# Wisp_v03.net
KiCad netlist of a schematic drawn in EAGLE
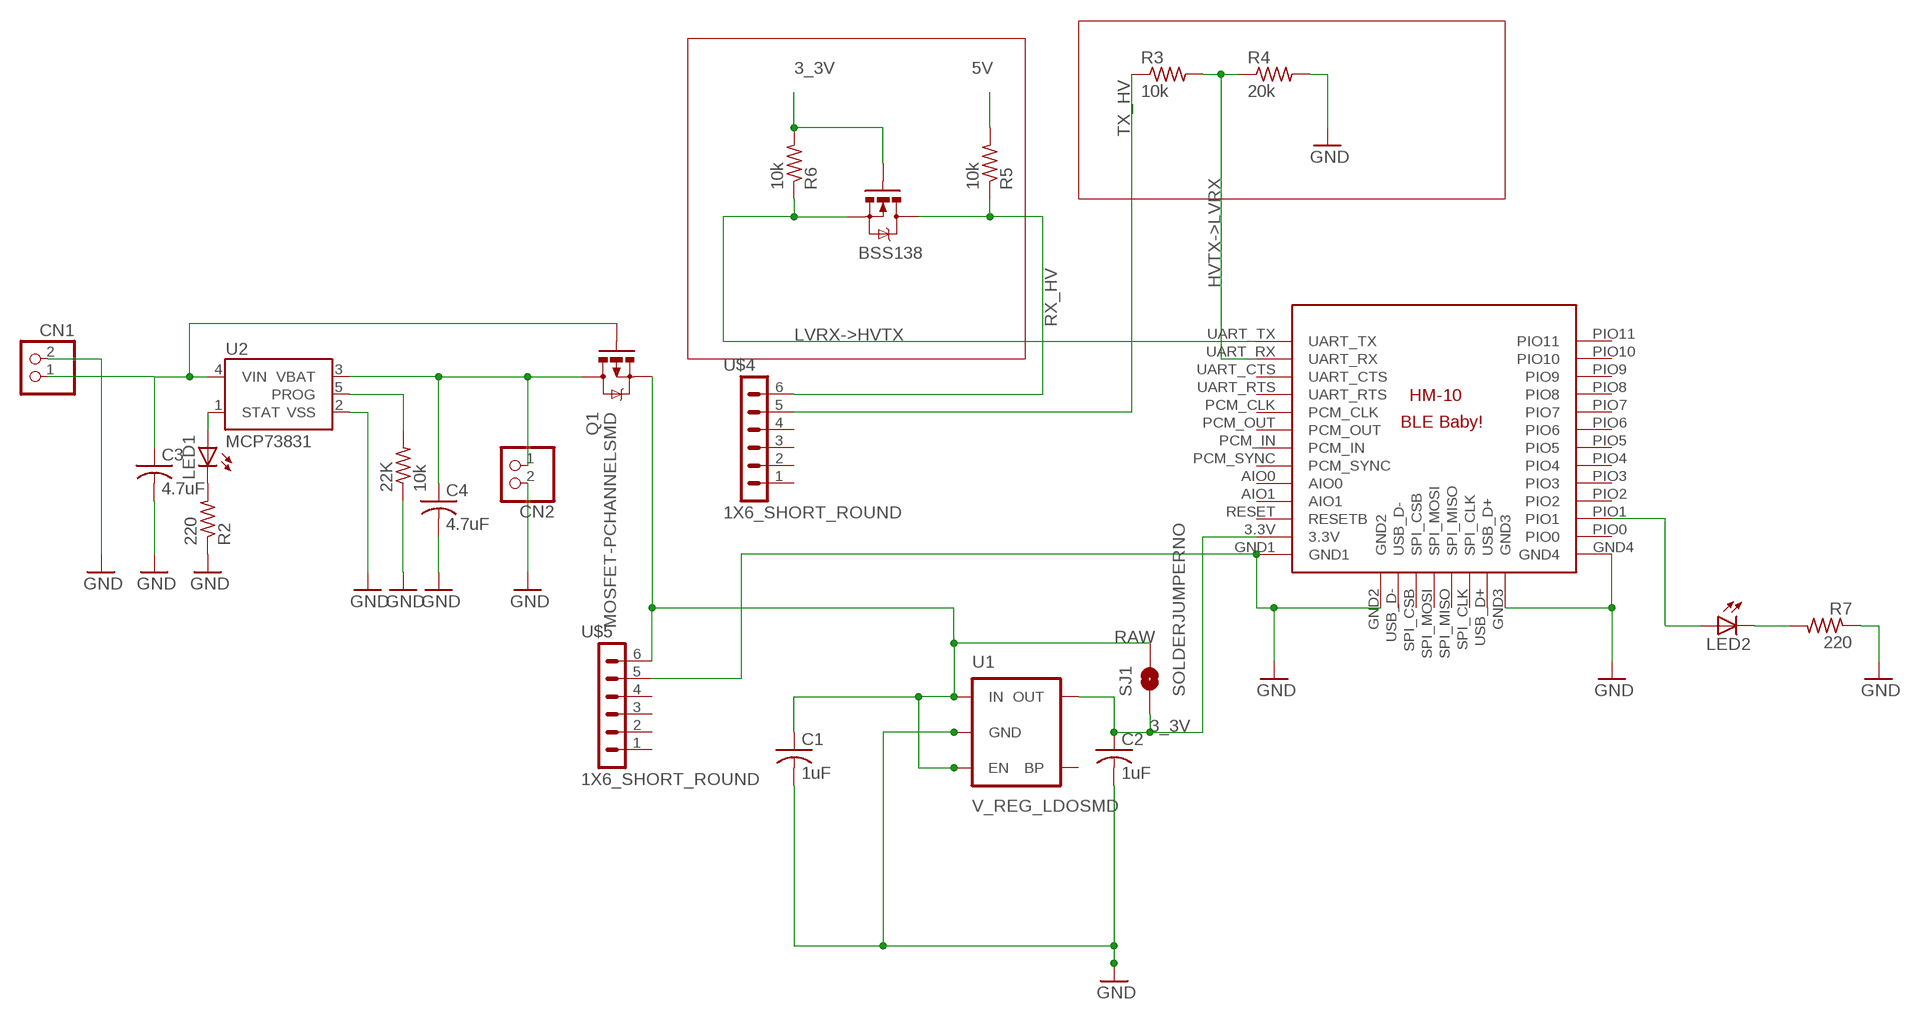
[diagram p0: schematic, sheet 1]

(export (version "E")
  (design (tool "Eeschema 10.0.6"))
  (components
    (comp (ref "22K")
      (value "10k")
      (footprint "eagle-import:R0402")
      (libsource (lib "eagle-import") (part "R-US_R0402"))
    )
    (comp (ref "BSS138")
      (value "MOSFET-NCHANNELSMD")
      (footprint "eagle-import:SOT23-3")
      (libsource (lib "eagle-import") (part "MOSFET-NCHANNELSMD"))
    )
    (comp (ref "C1")
      (value "1uF")
      (footprint "eagle-import:C0805K")
      (libsource (lib "eagle-import") (part "C-USC0805K"))
    )
    (comp (ref "C2")
      (value "1uF")
      (footprint "eagle-import:C0805K")
      (libsource (lib "eagle-import") (part "C-USC0805K"))
    )
    (comp (ref "C3")
      (value "4.7uF")
      (footprint "eagle-import:C0805K")
      (libsource (lib "eagle-import") (part "C-USC0805K"))
    )
    (comp (ref "C4")
      (value "4.7uF")
      (footprint "eagle-import:C0805K")
      (libsource (lib "eagle-import") (part "C-USC0805K"))
    )
    (comp (ref "CN1")
      (value "JST_2PIN-THM")
      (footprint "eagle-import:JST-PH-2-THM")
      (libsource (lib "eagle-import") (part "JST_2PIN-THM"))
    )
    (comp (ref "CN2")
      (value "JST_2PIN-THM")
      (footprint "eagle-import:JST-PH-2-THM")
      (libsource (lib "eagle-import") (part "JST_2PIN-THM"))
    )
    (comp (ref "LED1")
      (value "LED0603")
      (footprint "eagle-import:LED-0603")
      (libsource (lib "eagle-import") (part "LED0603"))
    )
    (comp (ref "LED2")
      (value "LED0603")
      (footprint "eagle-import:LED-0603")
      (libsource (lib "eagle-import") (part "LED0603"))
    )
    (comp (ref "Q1")
      (value "MOSFET-PCHANNELSMD")
      (footprint "eagle-import:SOT23-3")
      (libsource (lib "eagle-import") (part "MOSFET-PCHANNELSMD"))
    )
    (comp (ref "R2")
      (value "220")
      (footprint "eagle-import:R0402")
      (libsource (lib "eagle-import") (part "R-US_R0402"))
    )
    (comp (ref "R3")
      (value "10k")
      (footprint "eagle-import:R0402")
      (libsource (lib "eagle-import") (part "R-US_R0402"))
    )
    (comp (ref "R4")
      (value "20k")
      (footprint "eagle-import:R0402")
      (libsource (lib "eagle-import") (part "R-US_R0402"))
    )
    (comp (ref "R5")
      (value "10k")
      (footprint "eagle-import:R0402")
      (libsource (lib "eagle-import") (part "R-US_R0402"))
    )
    (comp (ref "R6")
      (value "10k")
      (footprint "eagle-import:R0402")
      (libsource (lib "eagle-import") (part "R-US_R0402"))
    )
    (comp (ref "R7")
      (value "220")
      (footprint "eagle-import:R0402")
      (libsource (lib "eagle-import") (part "R-US_R0402"))
    )
    (comp (ref "SJ1")
      (value "SOLDERJUMPERNO")
      (footprint "eagle-import:SJ_2S-NO")
      (libsource (lib "eagle-import") (part "SOLDERJUMPERNO"))
    )
    (comp (ref "U$1")
      (value "BLE-HM-10")
      (footprint "eagle-import:BLE-HM-10")
      (libsource (lib "eagle-import") (part "BLE-HM-10"))
    )
    (comp (ref "U$4")
      (value "1X6_SHORT_ROUND")
      (footprint "eagle-import:1X6_SHORT_ROUND")
      (libsource (lib "eagle-import") (part "1X6_SHORT_ROUND"))
    )
    (comp (ref "U$5")
      (value "1X6_SHORT_ROUND")
      (footprint "eagle-import:1X6_SHORT_ROUND")
      (libsource (lib "eagle-import") (part "1X6_SHORT_ROUND"))
    )
    (comp (ref "U1")
      (value "V_REG_LDOSMD")
      (footprint "eagle-import:SOT23-5")
      (libsource (lib "eagle-import") (part "V_REG_LDOSMD"))
    )
    (comp (ref "U2")
      (value "MCP73831")
      (footprint "eagle-import:SOT23-5")
      (libsource (lib "eagle-import") (part "MCP73831"))
    )
  )
  (nets
    (net (code "1") (name "/3_3V") (class "Default")
      (node (ref "BSS138") (pin "1") (pinfunction "G_1") (pintype "passive"))
      (node (ref "C2") (pin "1") (pinfunction "1_1") (pintype "passive"))
      (node (ref "R6") (pin "2") (pinfunction "2_2") (pintype "passive"))
      (node (ref "SJ1") (pin "1") (pinfunction "1_1") (pintype "passive"))
      (node (ref "U$1") (pin "3.3V") (pinfunction "3.3V_3.3V") (pintype "bidirectional"))
      (node (ref "U1") (pin "5") (pinfunction "OUT_5") (pintype "passive"))
    )
    (net (code "2") (name "/5V") (class "Default")
      (node (ref "R5") (pin "2") (pinfunction "2_2") (pintype "passive"))
    )
    (net (code "3") (name "/HVTX->LVRX") (class "Default")
      (node (ref "R3") (pin "2") (pinfunction "2_2") (pintype "passive"))
      (node (ref "R4") (pin "1") (pinfunction "1_1") (pintype "passive"))
      (node (ref "U$1") (pin "UART_RX") (pinfunction "UART_RX_UART_RX") (pintype "bidirectional"))
    )
    (net (code "4") (name "/LVRX->HVTX") (class "Default")
      (node (ref "BSS138") (pin "2") (pinfunction "S_2") (pintype "passive"))
      (node (ref "R6") (pin "1") (pinfunction "1_1") (pintype "passive"))
      (node (ref "U$1") (pin "UART_TX") (pinfunction "UART_TX_UART_TX") (pintype "bidirectional"))
    )
    (net (code "5") (name "/RAW") (class "Default")
      (node (ref "C1") (pin "1") (pinfunction "1_1") (pintype "passive"))
      (node (ref "Q1") (pin "2") (pinfunction "S_2") (pintype "passive"))
      (node (ref "SJ1") (pin "2") (pinfunction "2_2") (pintype "passive"))
      (node (ref "U$5") (pin "6") (pinfunction "6_6") (pintype "passive"))
      (node (ref "U1") (pin "1") (pinfunction "IN_1") (pintype "input"))
      (node (ref "U1") (pin "3") (pinfunction "EN_3") (pintype "input"))
    )
    (net (code "6") (name "/RX_HV") (class "Default")
      (node (ref "BSS138") (pin "3") (pinfunction "D_3") (pintype "passive"))
      (node (ref "R5") (pin "1") (pinfunction "1_1") (pintype "passive"))
      (node (ref "U$4") (pin "6") (pinfunction "6_6") (pintype "passive"))
    )
    (net (code "7") (name "/TX_HV") (class "Default")
      (node (ref "R3") (pin "1") (pinfunction "1_1") (pintype "passive"))
      (node (ref "U$4") (pin "5") (pinfunction "5_5") (pintype "passive"))
    )
    (net (code "8") (name "GND") (class "Default")
      (node (ref "22K") (pin "1") (pinfunction "1_1") (pintype "passive"))
      (node (ref "C1") (pin "2") (pinfunction "2_2") (pintype "passive"))
      (node (ref "C2") (pin "2") (pinfunction "2_2") (pintype "passive"))
      (node (ref "C3") (pin "2") (pinfunction "2_2") (pintype "passive"))
      (node (ref "C4") (pin "2") (pinfunction "2_2") (pintype "passive"))
      (node (ref "CN1") (pin "2") (pinfunction "1_2") (pintype "passive"))
      (node (ref "CN2") (pin "2") (pinfunction "1_2") (pintype "passive"))
      (node (ref "R2") (pin "1") (pinfunction "1_1") (pintype "passive"))
      (node (ref "R4") (pin "2") (pinfunction "2_2") (pintype "passive"))
      (node (ref "R7") (pin "1") (pinfunction "1_1") (pintype "passive"))
      (node (ref "U$1") (pin "GND1") (pinfunction "GND1_GND1") (pintype "bidirectional"))
      (node (ref "U$1") (pin "GND2") (pinfunction "GND2_GND2") (pintype "bidirectional"))
      (node (ref "U$1") (pin "GND3") (pinfunction "GND3_GND3") (pintype "bidirectional"))
      (node (ref "U$1") (pin "GND4") (pinfunction "GND4_GND4") (pintype "bidirectional"))
      (node (ref "U$5") (pin "5") (pinfunction "5_5") (pintype "passive"))
      (node (ref "U1") (pin "2") (pinfunction "GND_2") (pintype "input"))
      (node (ref "U2") (pin "2") (pinfunction "VSS_2") (pintype "power_in"))
    )
    (net (code "9") (name "Net-(CN1-2)") (class "Default")
      (node (ref "C3") (pin "1") (pinfunction "1_1") (pintype "passive"))
      (node (ref "CN1") (pin "1") (pinfunction "2_1") (pintype "passive"))
      (node (ref "Q1") (pin "1") (pinfunction "G_1") (pintype "passive"))
      (node (ref "U2") (pin "4") (pinfunction "VIN_4") (pintype "power_in"))
    )
    (net (code "10") (name "Net-(CN2-2)") (class "Default")
      (node (ref "C4") (pin "1") (pinfunction "1_1") (pintype "passive"))
      (node (ref "CN2") (pin "1") (pinfunction "2_1") (pintype "passive"))
      (node (ref "Q1") (pin "3") (pinfunction "D_3") (pintype "passive"))
      (node (ref "U2") (pin "3") (pinfunction "VBAT_3") (pintype "power_in"))
    )
    (net (code "11") (name "Net-(LED1-PadC)") (class "Default")
      (node (ref "LED1") (pin "C") (pinfunction "C_C") (pintype "passive"))
      (node (ref "R2") (pin "2") (pinfunction "2_2") (pintype "passive"))
    )
    (net (code "12") (name "Net-(LED2-PadA)") (class "Default")
      (node (ref "LED2") (pin "A") (pinfunction "A_A") (pintype "passive"))
      (node (ref "U$1") (pin "PIO1") (pinfunction "PIO1_PIO1") (pintype "bidirectional"))
    )
    (net (code "13") (name "Net-(LED2-PadC)") (class "Default")
      (node (ref "LED2") (pin "C") (pinfunction "C_C") (pintype "passive"))
      (node (ref "R7") (pin "2") (pinfunction "2_2") (pintype "passive"))
    )
    (net (code "14") (name "Net-(U2-PROG)") (class "Default")
      (node (ref "22K") (pin "2") (pinfunction "2_2") (pintype "passive"))
      (node (ref "U2") (pin "5") (pinfunction "PROG_5") (pintype "input"))
    )
    (net (code "15") (name "Net-(U2-STAT)") (class "Default")
      (node (ref "LED1") (pin "A") (pinfunction "A_A") (pintype "passive"))
      (node (ref "U2") (pin "1") (pinfunction "STAT_1") (pintype "output"))
    )
    (net (code "16") (name "unconnected-(U$1-PadAIO0)") (class "Default")
      (node (ref "U$1") (pin "AIO0") (pinfunction "AIO0_AIO0") (pintype "bidirectional"))
    )
    (net (code "17") (name "unconnected-(U$1-PadAIO1)") (class "Default")
      (node (ref "U$1") (pin "AIO1") (pinfunction "AIO1_AIO1") (pintype "bidirectional"))
    )
    (net (code "18") (name "unconnected-(U$1-PadPCM_CLK)") (class "Default")
      (node (ref "U$1") (pin "PCM_CLK") (pinfunction "PCM_CLK_PCM_CLK") (pintype "bidirectional"))
    )
    (net (code "19") (name "unconnected-(U$1-PadPCM_IN)") (class "Default")
      (node (ref "U$1") (pin "PCM_IN") (pinfunction "PCM_IN_PCM_IN") (pintype "bidirectional"))
    )
    (net (code "20") (name "unconnected-(U$1-PadPCM_OUT)") (class "Default")
      (node (ref "U$1") (pin "PCM_OUT") (pinfunction "PCM_OUT_PCM_OUT") (pintype "bidirectional"))
    )
    (net (code "21") (name "unconnected-(U$1-PadPCM_SYNC)") (class "Default")
      (node (ref "U$1") (pin "PCM_SYNC") (pinfunction "PCM_SYNC_PCM_SYNC") (pintype "bidirectional"))
    )
    (net (code "22") (name "unconnected-(U$1-PadPIO0)") (class "Default")
      (node (ref "U$1") (pin "PIO0") (pinfunction "PIO0_PIO0") (pintype "bidirectional"))
    )
    (net (code "23") (name "unconnected-(U$1-PadPIO2)") (class "Default")
      (node (ref "U$1") (pin "PIO2") (pinfunction "PIO2_PIO2") (pintype "bidirectional"))
    )
    (net (code "24") (name "unconnected-(U$1-PadPIO3)") (class "Default")
      (node (ref "U$1") (pin "PIO3") (pinfunction "PIO3_PIO3") (pintype "bidirectional"))
    )
    (net (code "25") (name "unconnected-(U$1-PadPIO4)") (class "Default")
      (node (ref "U$1") (pin "PIO4") (pinfunction "PIO4_PIO4") (pintype "bidirectional"))
    )
    (net (code "26") (name "unconnected-(U$1-PadPIO5)") (class "Default")
      (node (ref "U$1") (pin "PIO5") (pinfunction "PIO5_PIO5") (pintype "bidirectional"))
    )
    (net (code "27") (name "unconnected-(U$1-PadPIO6)") (class "Default")
      (node (ref "U$1") (pin "PIO6") (pinfunction "PIO6_PIO6") (pintype "bidirectional"))
    )
    (net (code "28") (name "unconnected-(U$1-PadPIO7)") (class "Default")
      (node (ref "U$1") (pin "PIO7") (pinfunction "PIO7_PIO7") (pintype "bidirectional"))
    )
    (net (code "29") (name "unconnected-(U$1-PadPIO8)") (class "Default")
      (node (ref "U$1") (pin "PIO8") (pinfunction "PIO8_PIO8") (pintype "bidirectional"))
    )
    (net (code "30") (name "unconnected-(U$1-PadPIO9)") (class "Default")
      (node (ref "U$1") (pin "PIO9") (pinfunction "PIO9_PIO9") (pintype "bidirectional"))
    )
    (net (code "31") (name "unconnected-(U$1-PadPIO10)") (class "Default")
      (node (ref "U$1") (pin "PIO10") (pinfunction "PIO10_PIO10") (pintype "bidirectional"))
    )
    (net (code "32") (name "unconnected-(U$1-PadPIO11)") (class "Default")
      (node (ref "U$1") (pin "PIO11") (pinfunction "PIO11_PIO11") (pintype "bidirectional"))
    )
    (net (code "33") (name "unconnected-(U$1-PadSPI_CLK)") (class "Default")
      (node (ref "U$1") (pin "SPI_CLK") (pinfunction "SPI_CLK_SPI_CLK") (pintype "bidirectional"))
    )
    (net (code "34") (name "unconnected-(U$1-PadSPI_CSB)") (class "Default")
      (node (ref "U$1") (pin "SPI_CSB") (pinfunction "SPI_CSB_SPI_CSB") (pintype "bidirectional"))
    )
    (net (code "35") (name "unconnected-(U$1-PadSPI_MISO)") (class "Default")
      (node (ref "U$1") (pin "SPI_MISO") (pinfunction "SPI_MISO_SPI_MISO") (pintype "bidirectional"))
    )
    (net (code "36") (name "unconnected-(U$1-PadSPI_MOSI)") (class "Default")
      (node (ref "U$1") (pin "SPI_MOSI") (pinfunction "SPI_MOSI_SPI_MOSI") (pintype "bidirectional"))
    )
    (net (code "37") (name "unconnected-(U$1-PadUART_CTS)") (class "Default")
      (node (ref "U$1") (pin "UART_CTS") (pinfunction "UART_CTS_UART_CTS") (pintype "bidirectional"))
    )
    (net (code "38") (name "unconnected-(U$1-PadUART_RTS)") (class "Default")
      (node (ref "U$1") (pin "UART_RTS") (pinfunction "UART_RTS_UART_RTS") (pintype "bidirectional"))
    )
    (net (code "39") (name "unconnected-(U$1-PadUSB_D+)") (class "Default")
      (node (ref "U$1") (pin "USB_D+") (pinfunction "USB_D+_USB_D+") (pintype "bidirectional"))
    )
    (net (code "40") (name "unconnected-(U$1-PadUSB_D-)") (class "Default")
      (node (ref "U$1") (pin "USB_D-") (pinfunction "USB_D-_USB_D-") (pintype "bidirectional"))
    )
    (net (code "41") (name "unconnected-(U$1-RESETB-PadRESET)") (class "Default")
      (node (ref "U$1") (pin "RESET") (pinfunction "RESETB_RESET") (pintype "bidirectional"))
    )
    (net (code "42") (name "unconnected-(U$4-Pad1)") (class "Default")
      (node (ref "U$4") (pin "1") (pinfunction "1_1") (pintype "passive"))
    )
    (net (code "43") (name "unconnected-(U$4-Pad2)") (class "Default")
      (node (ref "U$4") (pin "2") (pinfunction "2_2") (pintype "passive"))
    )
    (net (code "44") (name "unconnected-(U$4-Pad3)") (class "Default")
      (node (ref "U$4") (pin "3") (pinfunction "3_3") (pintype "passive"))
    )
    (net (code "45") (name "unconnected-(U$4-Pad4)") (class "Default")
      (node (ref "U$4") (pin "4") (pinfunction "4_4") (pintype "passive"))
    )
    (net (code "46") (name "unconnected-(U$5-Pad1)") (class "Default")
      (node (ref "U$5") (pin "1") (pinfunction "1_1") (pintype "passive"))
    )
    (net (code "47") (name "unconnected-(U$5-Pad2)") (class "Default")
      (node (ref "U$5") (pin "2") (pinfunction "2_2") (pintype "passive"))
    )
    (net (code "48") (name "unconnected-(U$5-Pad3)") (class "Default")
      (node (ref "U$5") (pin "3") (pinfunction "3_3") (pintype "passive"))
    )
    (net (code "49") (name "unconnected-(U$5-Pad4)") (class "Default")
      (node (ref "U$5") (pin "4") (pinfunction "4_4") (pintype "passive"))
    )
    (net (code "50") (name "unconnected-(U1-BP-Pad4)") (class "Default")
      (node (ref "U1") (pin "4") (pinfunction "BP_4") (pintype "input"))
    )
  )
)
